# electronic_load.net
KiCad netlist of a schematic drawn in EAGLE
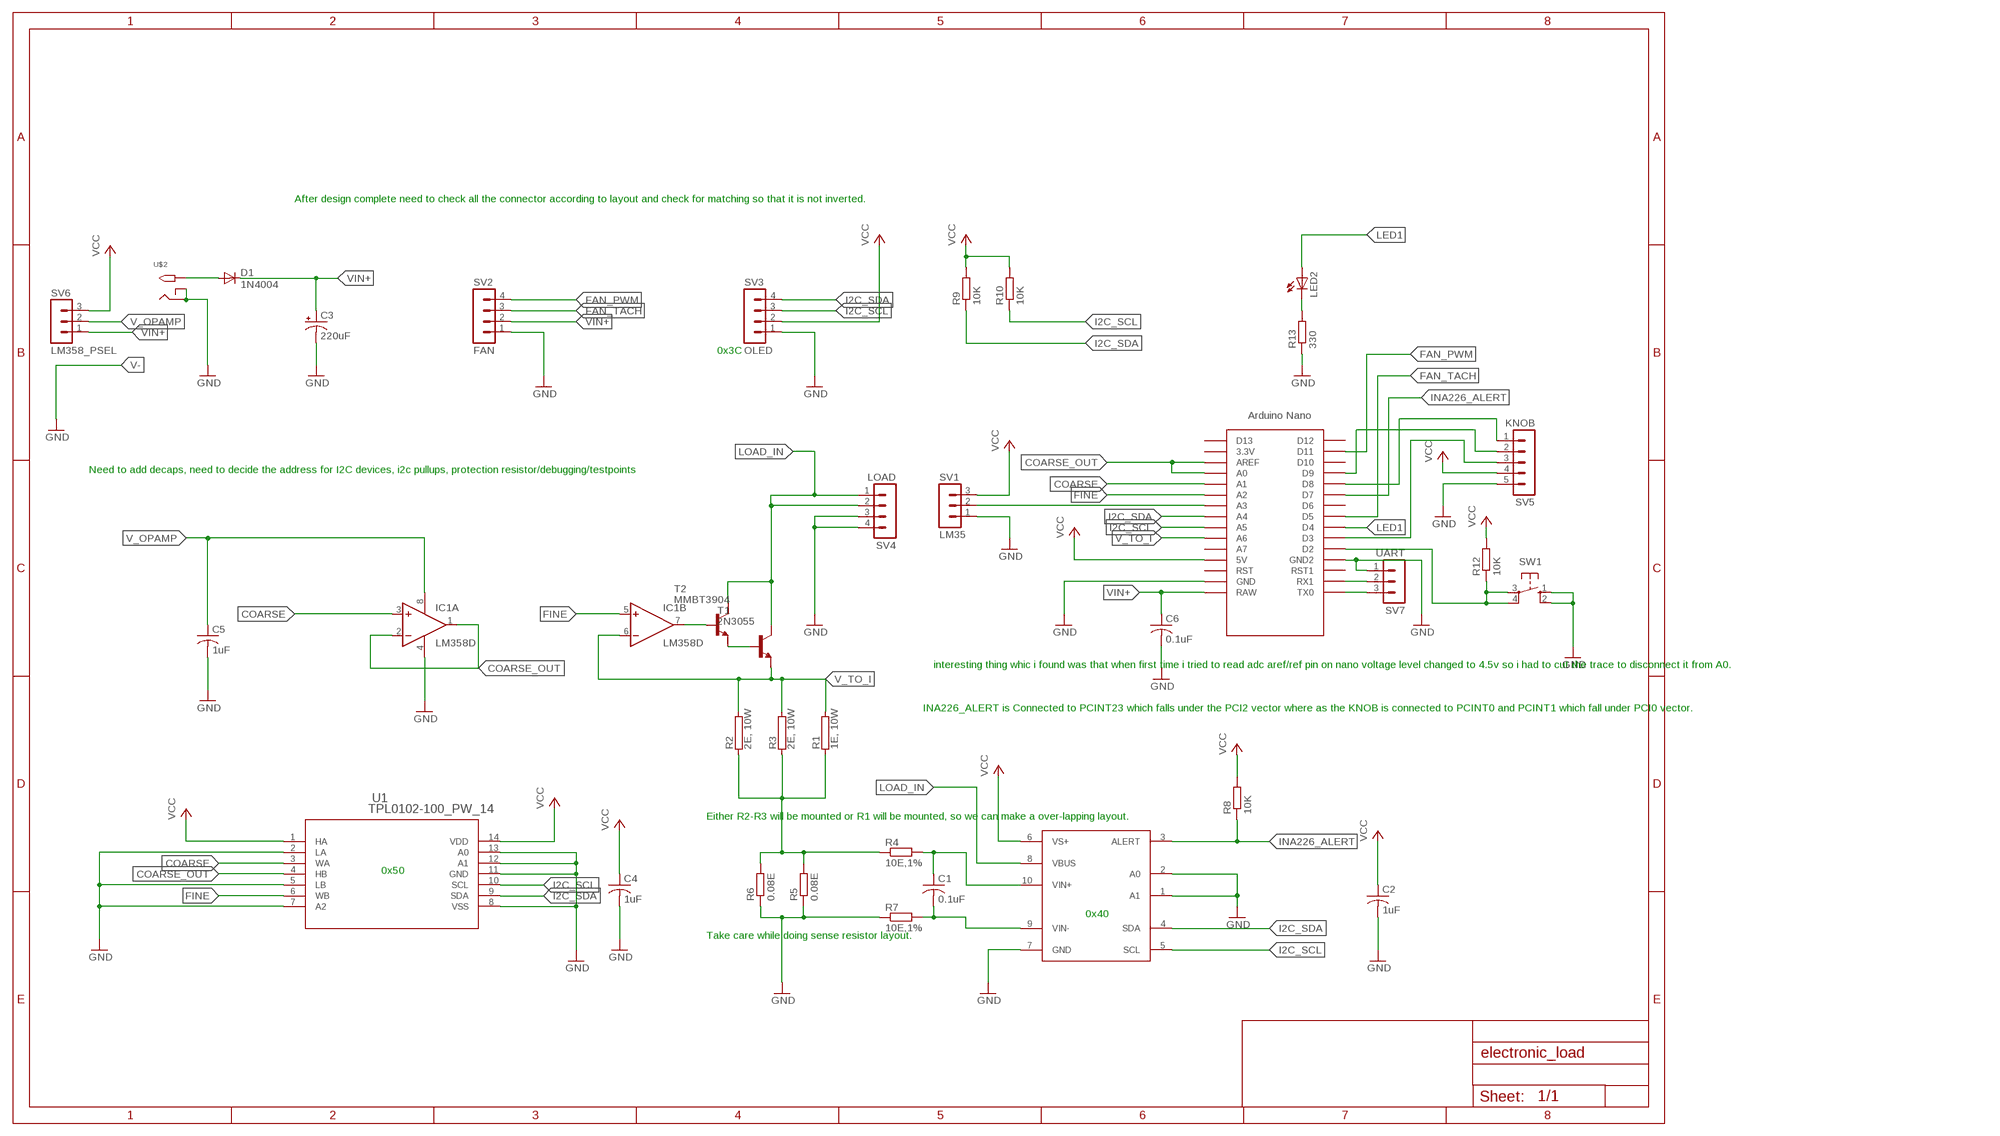
[diagram p0: schematic, sheet 1]

(export (version "E")
  (design (tool "Eeschema 10.0.6"))
  (components
    (comp (ref "C1")
      (value "0.1uF")
      (footprint "eagle-import:C0805")
      (libsource (lib "eagle-import") (part "C-USC0805"))
    )
    (comp (ref "C2")
      (value "1uF")
      (footprint "eagle-import:C0805")
      (libsource (lib "eagle-import") (part "C-USC0805"))
    )
    (comp (ref "C3")
      (value "220uF")
      (footprint "eagle-import:E3,5-8")
      (libsource (lib "eagle-import") (part "CPOL-USE3.5-8"))
    )
    (comp (ref "C4")
      (value "1uF")
      (footprint "eagle-import:C0805")
      (libsource (lib "eagle-import") (part "C-USC0805"))
    )
    (comp (ref "C5")
      (value "1uF")
      (footprint "eagle-import:C1206")
      (libsource (lib "eagle-import") (part "C-USC1206"))
    )
    (comp (ref "C6")
      (value "0.1uF")
      (footprint "eagle-import:C1206")
      (libsource (lib "eagle-import") (part "C-USC1206"))
    )
    (comp (ref "D1")
      (value "1N4004")
      (footprint "eagle-import:DO41-10")
      (libsource (lib "eagle-import") (part "1N4004"))
    )
    (comp (ref "IC1")
      (value "LM358D")
      (footprint "eagle-import:SO08")
      (libsource (lib "eagle-import") (part "LM358D"))
    )
    (comp (ref "LED2")
      (value "LED3MM")
      (footprint "eagle-import:LED3MM")
      (libsource (lib "eagle-import") (part "LED3MM"))
    )
    (comp (ref "R1")
      (value "1E, 10W")
      (footprint "eagle-import:AC10")
      (libsource (lib "eagle-import") (part "RAC10"))
    )
    (comp (ref "R2")
      (value "2E, 10W")
      (footprint "eagle-import:CA4150")
      (libsource (lib "eagle-import") (part "RCA4150"))
    )
    (comp (ref "R3")
      (value "2E, 10W")
      (footprint "eagle-import:CA4150")
      (libsource (lib "eagle-import") (part "RCA4150"))
    )
    (comp (ref "R4")
      (value "10E,1%")
      (footprint "eagle-import:R0805")
      (libsource (lib "eagle-import") (part "resistor_R-EU_R0805"))
    )
    (comp (ref "R5")
      (value "0.08E")
      (footprint "eagle-import:R2512")
      (libsource (lib "eagle-import") (part "R-EU_R2512"))
    )
    (comp (ref "R6")
      (value "0.08E")
      (footprint "eagle-import:R2512")
      (libsource (lib "eagle-import") (part "R-EU_R2512"))
    )
    (comp (ref "R7")
      (value "10E,1%")
      (footprint "eagle-import:R0805")
      (libsource (lib "eagle-import") (part "resistor_R-EU_R0805"))
    )
    (comp (ref "R8")
      (value "10K")
      (footprint "eagle-import:R0805")
      (libsource (lib "eagle-import") (part "R-EU_R0805"))
    )
    (comp (ref "R9")
      (value "10K")
      (footprint "eagle-import:R0805")
      (libsource (lib "eagle-import") (part "R-EU_R0805"))
    )
    (comp (ref "R10")
      (value "10K")
      (footprint "eagle-import:R0805")
      (libsource (lib "eagle-import") (part "R-EU_R0805"))
    )
    (comp (ref "R12")
      (value "10K")
      (footprint "eagle-import:R0805")
      (libsource (lib "eagle-import") (part "R-EU_R0805"))
    )
    (comp (ref "R13")
      (value "330")
      (footprint "eagle-import:R0805")
      (libsource (lib "eagle-import") (part "R-EU_R0805"))
    )
    (comp (ref "SV1")
      (value "LM35")
      (footprint "eagle-import:MA03-1")
      (libsource (lib "eagle-import") (part "MA03-1"))
    )
    (comp (ref "SV2")
      (value "FAN")
      (footprint "eagle-import:MA04-1")
      (libsource (lib "eagle-import") (part "MA04-1"))
    )
    (comp (ref "SV3")
      (value "OLED")
      (footprint "eagle-import:MA04-1")
      (libsource (lib "eagle-import") (part "MA04-1"))
    )
    (comp (ref "SV4")
      (value "LOAD")
      (footprint "eagle-import:MA04-1")
      (libsource (lib "eagle-import") (part "MA04-1"))
    )
    (comp (ref "SV5")
      (value "KNOB")
      (footprint "eagle-import:MA05-1")
      (libsource (lib "eagle-import") (part "MA05-1"))
    )
    (comp (ref "SV6")
      (value "LM358_PSEL")
      (footprint "eagle-import:MA03-1")
      (libsource (lib "eagle-import") (part "MA03-1"))
    )
    (comp (ref "SV7")
      (value "UART")
      (footprint "eagle-import:MA03-1")
      (libsource (lib "eagle-import") (part "MA03-1"))
    )
    (comp (ref "SW1")
      (value "10-XX")
      (footprint "eagle-import:B3F-10XX")
      (fields (field (name "MPN") "B3F-1000"))
      (libsource (lib "eagle-import") (part "10-XX"))
    )
    (comp (ref "T1")
      (value "2N3055")
      (footprint "eagle-import:TO3")
      (libsource (lib "eagle-import") (part "2N3055"))
    )
    (comp (ref "T2")
      (value "MMBT3904")
      (footprint "eagle-import:SOT23-BEC")
      (libsource (lib "eagle-import") (part "-NPN-SOT23-BECMMBT3904LT1"))
    )
    (comp (ref "U$1")
      (value "NANO")
      (footprint "eagle-import:NANO")
      (libsource (lib "eagle-import") (part "NANO"))
    )
    (comp (ref "U$2")
      (value "2.1MMJACKTHM")
      (footprint "eagle-import:PJ-102A")
      (libsource (lib "eagle-import") (part "2.1MMJACKTHM"))
    )
    (comp (ref "U1")
      (value "TPL0102-100_PW_14")
      (footprint "eagle-import:PW14")
      (fields
        (field (name "GENERIC_PART_NUMBER") "TPL0102-100")
        (field (name "MANUFACTURER") "Texas Instruments")
        (field (name "MANUFACTURER_PART_NUMBER") "tpl0102-100_pw_14")
      )
      (libsource (lib "eagle-import") (part "TPL0102-100_PW_14"))
    )
    (comp (ref "U2")
      (value "INA226AIDGST")
      (footprint "eagle-import:SOP50P490X110-10N")
      (libsource (lib "eagle-import") (part "INA226AIDGST"))
    )
  )
  (nets
    (net (code "1") (name "COARSE") (class "Default")
      (node (ref "IC1") (pin "3") (pinfunction "+IN_3") (pintype "input"))
      (node (ref "U$1") (pin "A1") (pinfunction "A1_A1") (pintype "bidirectional"))
      (node (ref "U1") (pin "3") (pinfunction "WA_3") (pintype "bidirectional"))
    )
    (net (code "2") (name "COARSE_OUT") (class "Default")
      (node (ref "IC1") (pin "1") (pinfunction "OUT_1") (pintype "output"))
      (node (ref "IC1") (pin "2") (pinfunction "-IN_2") (pintype "input"))
      (node (ref "U$1") (pin "A0") (pinfunction "A0_A0") (pintype "bidirectional"))
      (node (ref "U$1") (pin "AREF") (pinfunction "AREF_AREF") (pintype "bidirectional"))
      (node (ref "U1") (pin "4") (pinfunction "HB_4") (pintype "bidirectional"))
    )
    (net (code "3") (name "FAN_PWM") (class "Default")
      (node (ref "SV2") (pin "4") (pinfunction "4_4") (pintype "passive"))
      (node (ref "U$1") (pin "D11") (pinfunction "D11_D11") (pintype "bidirectional"))
    )
    (net (code "4") (name "FAN_TACH") (class "Default")
      (node (ref "SV2") (pin "3") (pinfunction "3_3") (pintype "passive"))
      (node (ref "U$1") (pin "D5") (pinfunction "D5_D5") (pintype "bidirectional"))
    )
    (net (code "5") (name "FINE") (class "Default")
      (node (ref "IC1") (pin "5") (pinfunction "+IN_5") (pintype "input"))
      (node (ref "U$1") (pin "A2") (pinfunction "A2_A2") (pintype "bidirectional"))
      (node (ref "U1") (pin "6") (pinfunction "WB_6") (pintype "bidirectional"))
    )
    (net (code "6") (name "I2C_SCL") (class "Default")
      (node (ref "R10") (pin "1") (pinfunction "1_1") (pintype "passive"))
      (node (ref "SV3") (pin "3") (pinfunction "3_3") (pintype "passive"))
      (node (ref "U$1") (pin "A5") (pinfunction "A5_A5") (pintype "bidirectional"))
      (node (ref "U1") (pin "10") (pinfunction "SCL_10") (pintype "input"))
      (node (ref "U2") (pin "5") (pinfunction "SCL_5") (pintype "input"))
    )
    (net (code "7") (name "I2C_SDA") (class "Default")
      (node (ref "R9") (pin "1") (pinfunction "1_1") (pintype "passive"))
      (node (ref "SV3") (pin "4") (pinfunction "4_4") (pintype "passive"))
      (node (ref "U$1") (pin "A4") (pinfunction "A4_A4") (pintype "bidirectional"))
      (node (ref "U1") (pin "9") (pinfunction "SDA_9") (pintype "bidirectional"))
      (node (ref "U2") (pin "4") (pinfunction "SDA_4") (pintype "bidirectional"))
    )
    (net (code "8") (name "INA226_ALERT") (class "Default")
      (node (ref "R8") (pin "1") (pinfunction "1_1") (pintype "passive"))
      (node (ref "U$1") (pin "D7") (pinfunction "D7_D7") (pintype "bidirectional"))
      (node (ref "U2") (pin "3") (pinfunction "ALERT_3") (pintype "output"))
    )
    (net (code "9") (name "LED1") (class "Default")
      (node (ref "LED2") (pin "A") (pinfunction "A_A") (pintype "passive"))
      (node (ref "U$1") (pin "D4") (pinfunction "D4_D4") (pintype "bidirectional"))
    )
    (net (code "10") (name "LOAD_IN") (class "Default")
      (node (ref "SV4") (pin "1") (pinfunction "1_1") (pintype "passive"))
      (node (ref "SV4") (pin "2") (pinfunction "2_2") (pintype "passive"))
      (node (ref "T1") (pin "C") (pinfunction "C_C") (pintype "passive"))
      (node (ref "T1") (pin "C/") (pinfunction "C_C/") (pintype "passive"))
      (node (ref "T2") (pin "C") (pinfunction "C_C") (pintype "passive"))
      (node (ref "U2") (pin "8") (pinfunction "VBUS_8") (pintype "input"))
    )
    (net (code "11") (name "Net-(D1-PadA)") (class "Default")
      (node (ref "D1") (pin "A") (pinfunction "A_A") (pintype "passive"))
      (node (ref "U$2") (pin "TIP") (pinfunction "TIP_TIP") (pintype "bidirectional"))
    )
    (net (code "12") (name "Net-(IC1B-OUT)") (class "Default")
      (node (ref "IC1") (pin "7") (pinfunction "OUT_7") (pintype "output"))
      (node (ref "T2") (pin "B") (pinfunction "B_B") (pintype "passive"))
    )
    (net (code "13") (name "Net-(LED2-C)") (class "Default")
      (node (ref "LED2") (pin "K") (pinfunction "C_K") (pintype "passive"))
      (node (ref "R13") (pin "2") (pinfunction "2_2") (pintype "passive"))
    )
    (net (code "14") (name "Net-(R1-Pad1)") (class "Default")
      (node (ref "R1") (pin "1") (pinfunction "1_1") (pintype "passive"))
      (node (ref "R2") (pin "1") (pinfunction "1_1") (pintype "passive"))
      (node (ref "R3") (pin "1") (pinfunction "1_1") (pintype "passive"))
      (node (ref "R4") (pin "1") (pinfunction "1_1") (pintype "passive"))
      (node (ref "R5") (pin "2") (pinfunction "2_2") (pintype "passive"))
      (node (ref "R6") (pin "2") (pinfunction "2_2") (pintype "passive"))
    )
    (net (code "15") (name "Net-(SV1-Pad2)") (class "Default")
      (node (ref "SV1") (pin "2") (pinfunction "2_2") (pintype "passive"))
      (node (ref "U$1") (pin "A3") (pinfunction "A3_A3") (pintype "bidirectional"))
    )
    (net (code "16") (name "Net-(SV5-Pad1)") (class "Default")
      (node (ref "SV5") (pin "1") (pinfunction "1_1") (pintype "passive"))
      (node (ref "U$1") (pin "D8") (pinfunction "D8_D8") (pintype "bidirectional"))
    )
    (net (code "17") (name "Net-(SV5-Pad2)") (class "Default")
      (node (ref "SV5") (pin "2") (pinfunction "2_2") (pintype "passive"))
      (node (ref "U$1") (pin "D9") (pinfunction "D9_D9") (pintype "bidirectional"))
    )
    (net (code "18") (name "Net-(SV5-Pad3)") (class "Default")
      (node (ref "SV5") (pin "3") (pinfunction "3_3") (pintype "passive"))
      (node (ref "U$1") (pin "D3") (pinfunction "D3_D3") (pintype "bidirectional"))
    )
    (net (code "19") (name "Net-(SV7-Pad2)") (class "Default")
      (node (ref "SV7") (pin "2") (pinfunction "2_2") (pintype "passive"))
      (node (ref "U$1") (pin "RX1") (pinfunction "RX1_RX1") (pintype "bidirectional"))
    )
    (net (code "20") (name "Net-(SV7-Pad3)") (class "Default")
      (node (ref "SV7") (pin "3") (pinfunction "3_3") (pintype "passive"))
      (node (ref "U$1") (pin "TX0") (pinfunction "TX0_TX0") (pintype "bidirectional"))
    )
    (net (code "21") (name "Net-(SW1-P)") (class "Default")
      (node (ref "R12") (pin "1") (pinfunction "1_1") (pintype "passive"))
      (node (ref "SW1") (pin "3") (pinfunction "P_3") (pintype "passive"))
      (node (ref "SW1") (pin "4") (pinfunction "P1_4") (pintype "passive"))
      (node (ref "U$1") (pin "D2") (pinfunction "D2_D2") (pintype "bidirectional"))
    )
    (net (code "22") (name "Net-(T1-PadB)") (class "Default")
      (node (ref "T1") (pin "B") (pinfunction "B_B") (pintype "passive"))
      (node (ref "T2") (pin "E") (pinfunction "E_E") (pintype "passive"))
    )
    (net (code "23") (name "Net-(U2-VIN+)") (class "Default")
      (node (ref "C1") (pin "1") (pinfunction "1_1") (pintype "passive"))
      (node (ref "R4") (pin "2") (pinfunction "2_2") (pintype "passive"))
      (node (ref "U2") (pin "10") (pinfunction "VIN+_10") (pintype "input"))
    )
    (net (code "24") (name "Net-(U2-VIN-)") (class "Default")
      (node (ref "C1") (pin "2") (pinfunction "2_2") (pintype "passive"))
      (node (ref "R7") (pin "2") (pinfunction "2_2") (pintype "passive"))
      (node (ref "U2") (pin "9") (pinfunction "VIN-_9") (pintype "input"))
    )
    (net (code "25") (name "V-") (class "Default")
      (node (ref "C2") (pin "2") (pinfunction "2_2") (pintype "passive"))
      (node (ref "C3") (pin "-") (pinfunction "-_-") (pintype "passive"))
      (node (ref "C4") (pin "2") (pinfunction "2_2") (pintype "passive"))
      (node (ref "C5") (pin "2") (pinfunction "2_2") (pintype "passive"))
      (node (ref "C6") (pin "2") (pinfunction "2_2") (pintype "passive"))
      (node (ref "IC1") (pin "4") (pinfunction "V-_4") (pintype "power_in"))
      (node (ref "R13") (pin "1") (pinfunction "1_1") (pintype "passive"))
      (node (ref "R5") (pin "1") (pinfunction "1_1") (pintype "passive"))
      (node (ref "R6") (pin "1") (pinfunction "1_1") (pintype "passive"))
      (node (ref "R7") (pin "1") (pinfunction "1_1") (pintype "passive"))
      (node (ref "SV1") (pin "1") (pinfunction "1_1") (pintype "passive"))
      (node (ref "SV2") (pin "1") (pinfunction "1_1") (pintype "passive"))
      (node (ref "SV3") (pin "1") (pinfunction "1_1") (pintype "passive"))
      (node (ref "SV4") (pin "3") (pinfunction "3_3") (pintype "passive"))
      (node (ref "SV4") (pin "4") (pinfunction "4_4") (pintype "passive"))
      (node (ref "SV5") (pin "5") (pinfunction "5_5") (pintype "passive"))
      (node (ref "SV7") (pin "1") (pinfunction "1_1") (pintype "passive"))
      (node (ref "SW1") (pin "1") (pinfunction "S_1") (pintype "passive"))
      (node (ref "SW1") (pin "2") (pinfunction "S1_2") (pintype "passive"))
      (node (ref "U$1") (pin "GND") (pinfunction "GND_GND") (pintype "bidirectional"))
      (node (ref "U$1") (pin "GND1") (pinfunction "GND2_GND1") (pintype "bidirectional"))
      (node (ref "U$2") (pin "RING") (pinfunction "RING_RING") (pintype "bidirectional"))
      (node (ref "U$2") (pin "RING_SW") (pinfunction "RING_SW_RING_SW") (pintype "bidirectional"))
      (node (ref "U1") (pin "11") (pinfunction "GND_11") (pintype "power_in"))
      (node (ref "U1") (pin "12") (pinfunction "A1_12") (pintype "input"))
      (node (ref "U1") (pin "13") (pinfunction "A0_13") (pintype "input"))
      (node (ref "U1") (pin "2") (pinfunction "LA_2") (pintype "bidirectional"))
      (node (ref "U1") (pin "5") (pinfunction "LB_5") (pintype "bidirectional"))
      (node (ref "U1") (pin "7") (pinfunction "A2_7") (pintype "input"))
      (node (ref "U1") (pin "8") (pinfunction "VSS_8") (pintype "power_in"))
      (node (ref "U2") (pin "1") (pinfunction "A1_1") (pintype "passive"))
      (node (ref "U2") (pin "2") (pinfunction "A0_2") (pintype "passive"))
      (node (ref "U2") (pin "7") (pinfunction "GND_7") (pintype "passive"))
    )
    (net (code "26") (name "VCC") (class "Default")
      (node (ref "C2") (pin "1") (pinfunction "1_1") (pintype "passive"))
      (node (ref "C4") (pin "1") (pinfunction "1_1") (pintype "passive"))
      (node (ref "R10") (pin "2") (pinfunction "2_2") (pintype "passive"))
      (node (ref "R12") (pin "2") (pinfunction "2_2") (pintype "passive"))
      (node (ref "R8") (pin "2") (pinfunction "2_2") (pintype "passive"))
      (node (ref "R9") (pin "2") (pinfunction "2_2") (pintype "passive"))
      (node (ref "SV1") (pin "3") (pinfunction "3_3") (pintype "passive"))
      (node (ref "SV3") (pin "2") (pinfunction "2_2") (pintype "passive"))
      (node (ref "SV5") (pin "4") (pinfunction "4_4") (pintype "passive"))
      (node (ref "SV6") (pin "3") (pinfunction "3_3") (pintype "passive"))
      (node (ref "U$1") (pin "5V") (pinfunction "5V_5V") (pintype "bidirectional"))
      (node (ref "U1") (pin "1") (pinfunction "HA_1") (pintype "bidirectional"))
      (node (ref "U1") (pin "14") (pinfunction "VDD_14") (pintype "power_in"))
      (node (ref "U2") (pin "6") (pinfunction "VS+_6") (pintype "power_in"))
    )
    (net (code "27") (name "VIN+") (class "Default")
      (node (ref "C3") (pin "+") (pinfunction "+_+") (pintype "passive"))
      (node (ref "C6") (pin "1") (pinfunction "1_1") (pintype "passive"))
      (node (ref "D1") (pin "C") (pinfunction "C_C") (pintype "passive"))
      (node (ref "SV2") (pin "2") (pinfunction "2_2") (pintype "passive"))
      (node (ref "SV6") (pin "1") (pinfunction "1_1") (pintype "passive"))
      (node (ref "U$1") (pin "RAW") (pinfunction "RAW_RAW") (pintype "bidirectional"))
    )
    (net (code "28") (name "V_OPAMP") (class "Default")
      (node (ref "C5") (pin "1") (pinfunction "1_1") (pintype "passive"))
      (node (ref "IC1") (pin "8") (pinfunction "V+_8") (pintype "power_in"))
      (node (ref "SV6") (pin "2") (pinfunction "2_2") (pintype "passive"))
    )
    (net (code "29") (name "V_TO_I") (class "Default")
      (node (ref "IC1") (pin "6") (pinfunction "-IN_6") (pintype "input"))
      (node (ref "R1") (pin "2") (pinfunction "2_2") (pintype "passive"))
      (node (ref "R2") (pin "2") (pinfunction "2_2") (pintype "passive"))
      (node (ref "R3") (pin "2") (pinfunction "2_2") (pintype "passive"))
      (node (ref "T1") (pin "E") (pinfunction "E_E") (pintype "passive"))
      (node (ref "U$1") (pin "A6") (pinfunction "A6_A6") (pintype "bidirectional"))
    )
    (net (code "30") (name "unconnected-(U$1-Pad3.3V)") (class "Default")
      (node (ref "U$1") (pin "3.3V") (pinfunction "3.3V_3.3V") (pintype "bidirectional"))
    )
    (net (code "31") (name "unconnected-(U$1-PadA7)") (class "Default")
      (node (ref "U$1") (pin "A7") (pinfunction "A7_A7") (pintype "bidirectional"))
    )
    (net (code "32") (name "unconnected-(U$1-PadD6)") (class "Default")
      (node (ref "U$1") (pin "D6") (pinfunction "D6_D6") (pintype "bidirectional"))
    )
    (net (code "33") (name "unconnected-(U$1-PadD10)") (class "Default")
      (node (ref "U$1") (pin "D10") (pinfunction "D10_D10") (pintype "bidirectional"))
    )
    (net (code "34") (name "unconnected-(U$1-PadD12)") (class "Default")
      (node (ref "U$1") (pin "D12") (pinfunction "D12_D12") (pintype "bidirectional"))
    )
    (net (code "35") (name "unconnected-(U$1-PadD13)") (class "Default")
      (node (ref "U$1") (pin "D13") (pinfunction "D13_D13") (pintype "bidirectional"))
    )
    (net (code "36") (name "unconnected-(U$1-PadRST)") (class "Default")
      (node (ref "U$1") (pin "RST") (pinfunction "RST_RST") (pintype "bidirectional"))
    )
    (net (code "37") (name "unconnected-(U$1-PadRST1)") (class "Default")
      (node (ref "U$1") (pin "RST1") (pinfunction "RST1_RST1") (pintype "bidirectional"))
    )
  )
)
